# Power_Supplies.net
KiCad netlist of a schematic drawn in Altium Designer
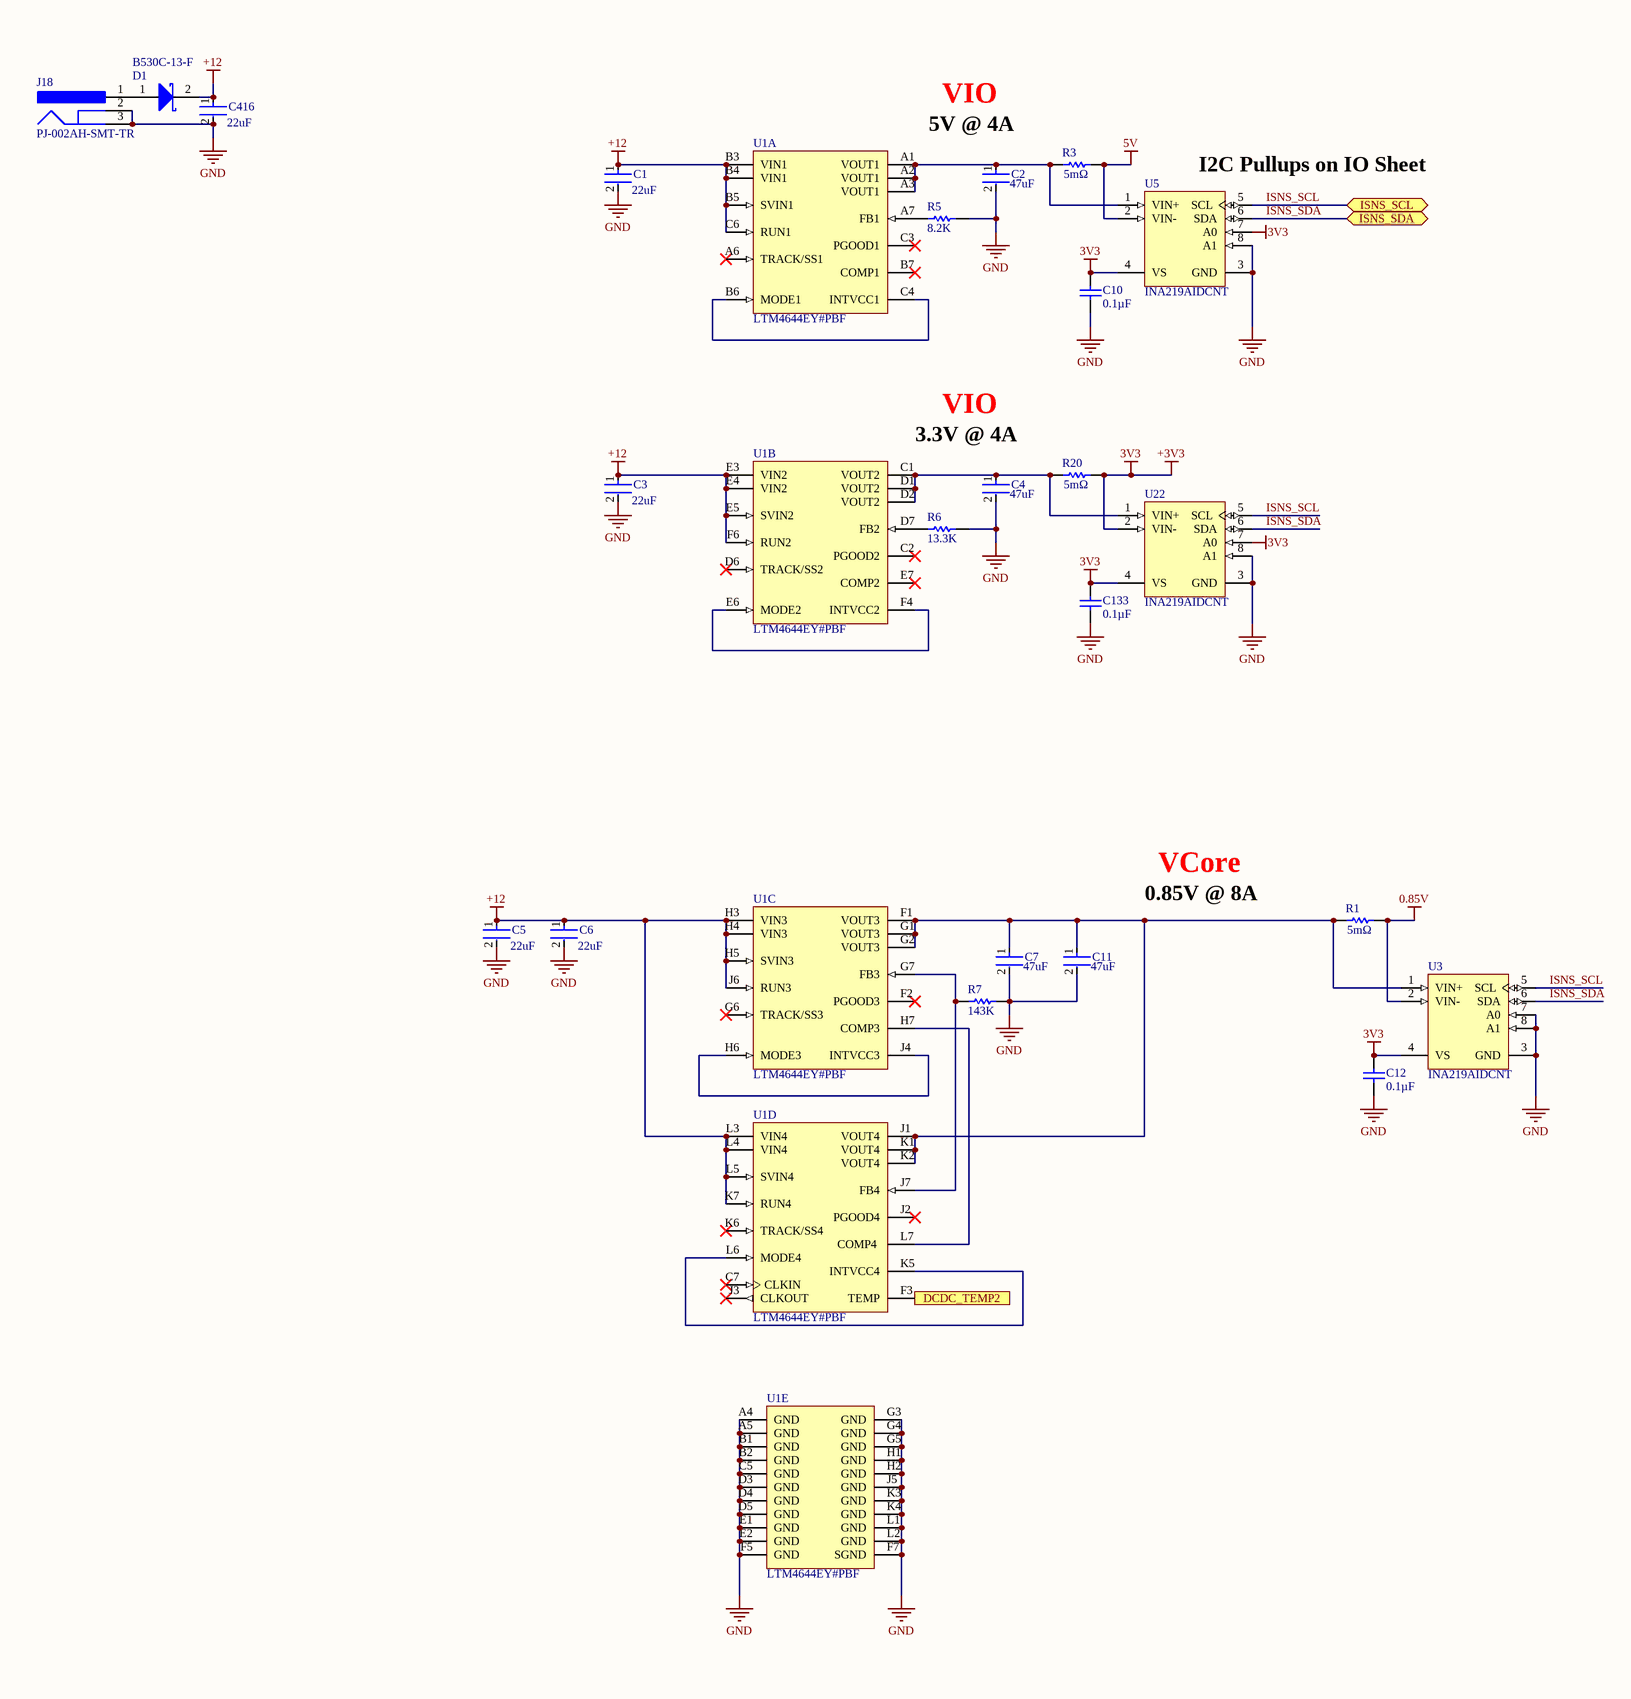
[diagram p0: Power Supplies.SchDoc, left]
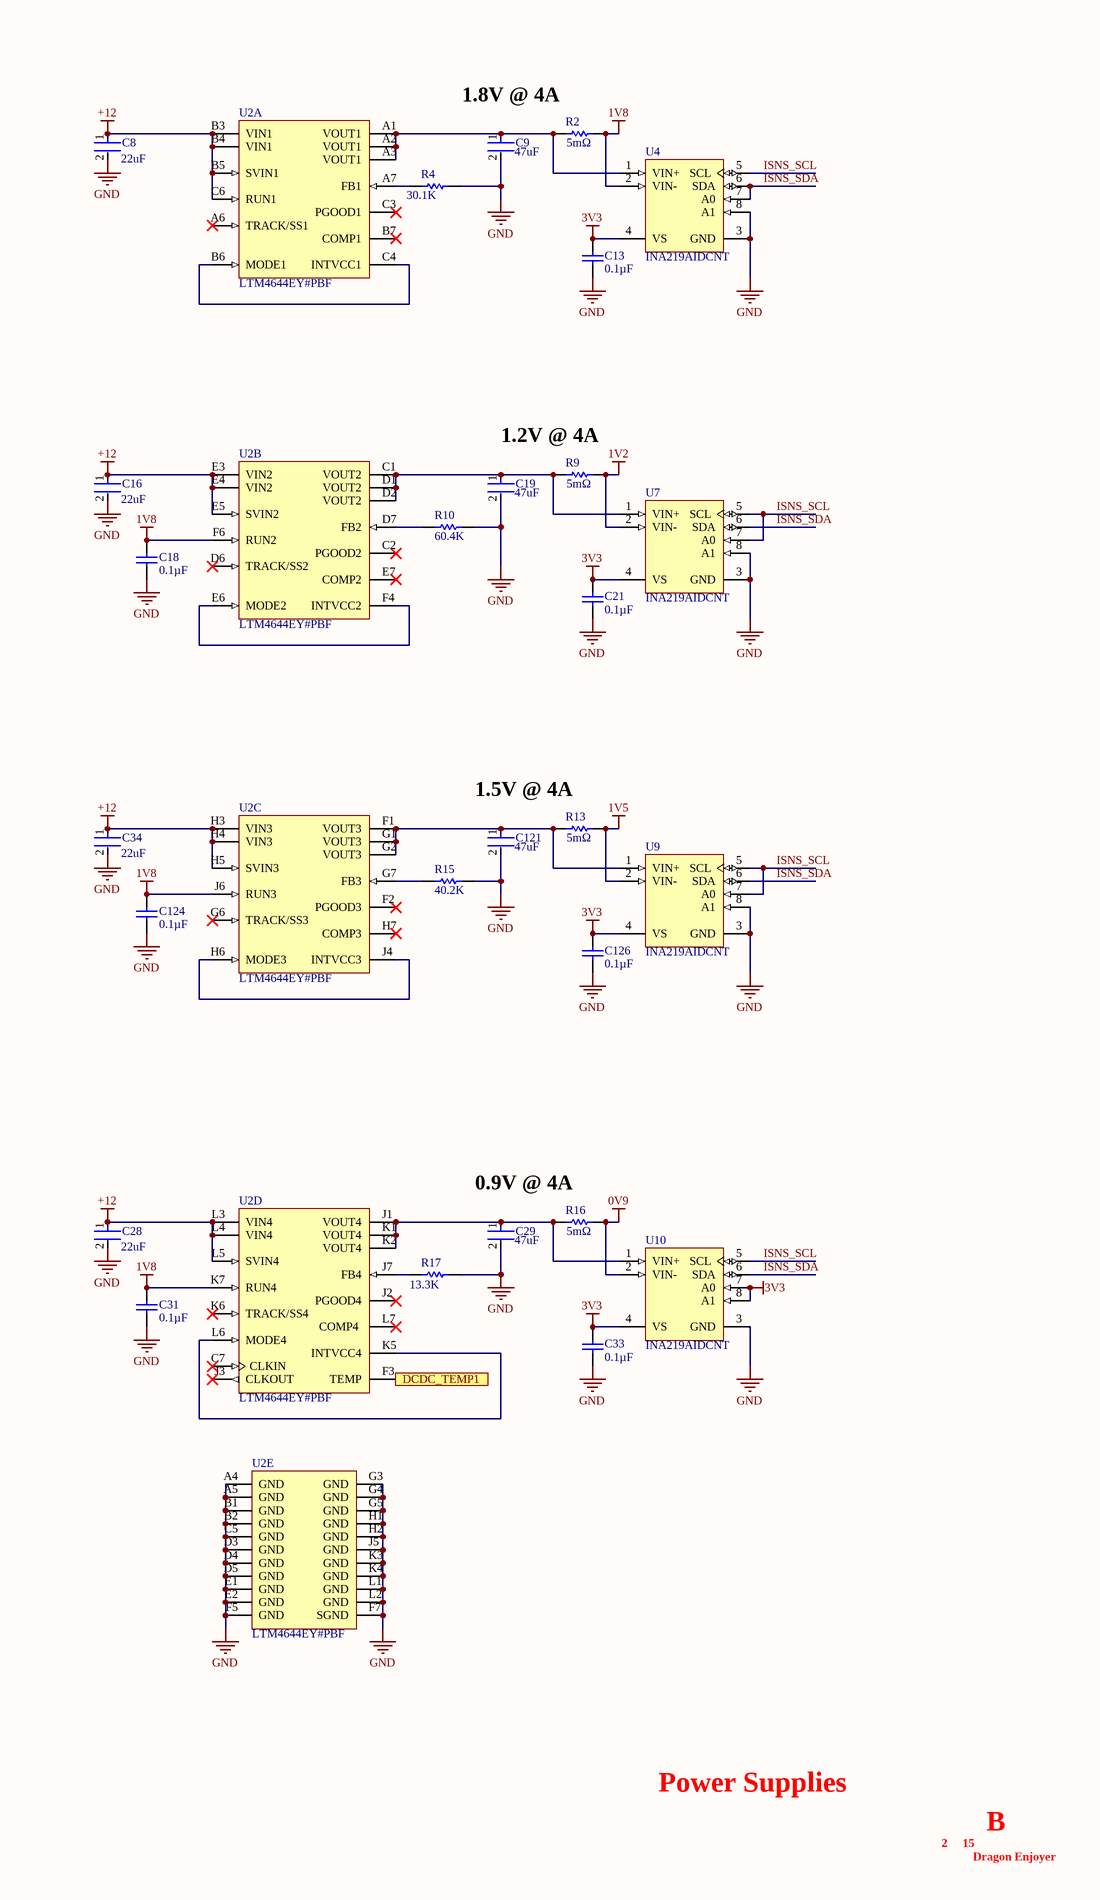
[diagram p1: Power Supplies.SchDoc, right]

(export (version "E")
  (design (tool "Eeschema 10.0.6"))
  (components
    (comp (ref "C1")
      (value "22uF")
      (footprint "FP-CL31H-0_2-MFG")
      (description "CAP CER 22UF 25V X5R 1206")
      (fields
        (field (name "OCTOPART") "https://octopart.com/cl31a226kahnnne-samsung-19832795")
        (field (name "TOLERANCE") "10%")
      )
      (libsource (lib "Altium Content Vault") (part "11868f565c42a9108669ba33697ecf6"))
    )
    (comp (ref "C2")
      (value "GRM31CR60J476ME19L")
      (footprint "FP-GRM31C-0_2-e0_3_0_8-IPC_C")
      (description "Chip Multilayer Ceramic Capacitors for General Purpose, 1206, 47uF, X5R, 15%, 20%, 6.3V")
      (fields
        (field (name "TOLERANCE") "20%")
        (field (name "VOLTAGE") "6.3V")
        (field (name "CAPACITANCE") "47uF")
      )
      (libsource (lib "Altium Content Vault") (part "02cd4be3c70576c341d710602a673aa"))
    )
    (comp (ref "C3")
      (value "22uF")
      (footprint "FP-CL31H-0_2-MFG")
      (description "CAP CER 22UF 25V X5R 1206")
      (fields
        (field (name "OCTOPART") "https://octopart.com/cl31a226kahnnne-samsung-19832795")
        (field (name "TOLERANCE") "10%")
      )
      (libsource (lib "Altium Content Vault") (part "11868f565c42a9108669ba33697ecf6"))
    )
    (comp (ref "C4")
      (value "GRM31CR60J476ME19L")
      (footprint "FP-GRM31C-0_2-e0_3_0_8-IPC_C")
      (description "Chip Multilayer Ceramic Capacitors for General Purpose, 1206, 47uF, X5R, 15%, 20%, 6.3V")
      (fields
        (field (name "TOLERANCE") "20%")
        (field (name "VOLTAGE") "6.3V")
        (field (name "CAPACITANCE") "47uF")
      )
      (libsource (lib "Altium Content Vault") (part "02cd4be3c70576c341d710602a673aa"))
    )
    (comp (ref "C5")
      (value "22uF")
      (footprint "FP-CL31H-0_2-MFG")
      (description "CAP CER 22UF 25V X5R 1206")
      (fields
        (field (name "OCTOPART") "https://octopart.com/cl31a226kahnnne-samsung-19832795")
        (field (name "TOLERANCE") "10%")
      )
      (libsource (lib "Altium Content Vault") (part "11868f565c42a9108669ba33697ecf6"))
    )
    (comp (ref "C6")
      (value "22uF")
      (footprint "FP-CL31H-0_2-MFG")
      (description "CAP CER 22UF 25V X5R 1206")
      (fields
        (field (name "OCTOPART") "https://octopart.com/cl31a226kahnnne-samsung-19832795")
        (field (name "TOLERANCE") "10%")
      )
      (libsource (lib "Altium Content Vault") (part "11868f565c42a9108669ba33697ecf6"))
    )
    (comp (ref "C7")
      (value "GRM31CR60J476ME19L")
      (footprint "FP-GRM31C-0_2-e0_3_0_8-IPC_C")
      (description "Chip Multilayer Ceramic Capacitors for General Purpose, 1206, 47uF, X5R, 15%, 20%, 6.3V")
      (fields
        (field (name "TOLERANCE") "20%")
        (field (name "VOLTAGE") "6.3V")
        (field (name "CAPACITANCE") "47uF")
      )
      (libsource (lib "Altium Content Vault") (part "02cd4be3c70576c341d710602a673aa"))
    )
    (comp (ref "C8")
      (value "22uF")
      (footprint "FP-CL31H-0_2-MFG")
      (description "CAP CER 22UF 25V X5R 1206")
      (fields
        (field (name "OCTOPART") "https://octopart.com/cl31a226kahnnne-samsung-19832795")
        (field (name "TOLERANCE") "10%")
      )
      (libsource (lib "Altium Content Vault") (part "11868f565c42a9108669ba33697ecf6"))
    )
    (comp (ref "C9")
      (value "GRM31CR60J476ME19L")
      (footprint "FP-GRM31C-0_2-e0_3_0_8-IPC_C")
      (description "Chip Multilayer Ceramic Capacitors for General Purpose, 1206, 47uF, X5R, 15%, 20%, 6.3V")
      (fields
        (field (name "TOLERANCE") "20%")
        (field (name "VOLTAGE") "6.3V")
        (field (name "CAPACITANCE") "47uF")
      )
      (libsource (lib "Altium Content Vault") (part "02cd4be3c70576c341d710602a673aa"))
    )
    (comp (ref "C10")
      (value "CC0402ZRY5V8BB104")
      (footprint "CAPC1005X55X25LL05T05")
      (description "Chip Capacitor, 100 nF, -20% to 80%, 25 V, -30 to 85 degC, 0402 (1005 Metric), RoHS, Tape and Reel")
      (fields
        (field (name "TOLERANCE") "-20%,+80%")
        (field (name "CAPACITANCE") "0.1µF")
        (field (name "MANUFACTURER") "Yageo")
      )
      (libsource (lib "Altium Content Vault") (part "CAP-NP-2"))
    )
    (comp (ref "C11")
      (value "GRM31CR60J476ME19L")
      (footprint "FP-GRM31C-0_2-e0_3_0_8-IPC_C")
      (description "Chip Multilayer Ceramic Capacitors for General Purpose, 1206, 47uF, X5R, 15%, 20%, 6.3V")
      (fields
        (field (name "TOLERANCE") "20%")
        (field (name "VOLTAGE") "6.3V")
        (field (name "CAPACITANCE") "47uF")
      )
      (libsource (lib "Altium Content Vault") (part "02cd4be3c70576c341d710602a673aa"))
    )
    (comp (ref "C12")
      (value "CC0402ZRY5V8BB104")
      (footprint "CAPC1005X55X25LL05T05")
      (description "Chip Capacitor, 100 nF, -20% to 80%, 25 V, -30 to 85 degC, 0402 (1005 Metric), RoHS, Tape and Reel")
      (fields
        (field (name "TOLERANCE") "-20%,+80%")
        (field (name "CAPACITANCE") "0.1µF")
        (field (name "MANUFACTURER") "Yageo")
      )
      (libsource (lib "Altium Content Vault") (part "CAP-NP-2"))
    )
    (comp (ref "C13")
      (value "CC0402ZRY5V8BB104")
      (footprint "CAPC1005X55X25LL05T05")
      (description "Chip Capacitor, 100 nF, -20% to 80%, 25 V, -30 to 85 degC, 0402 (1005 Metric), RoHS, Tape and Reel")
      (fields
        (field (name "TOLERANCE") "-20%,+80%")
        (field (name "CAPACITANCE") "0.1µF")
        (field (name "MANUFACTURER") "Yageo")
      )
      (libsource (lib "Altium Content Vault") (part "CAP-NP-2"))
    )
    (comp (ref "C16")
      (value "22uF")
      (footprint "FP-CL31H-0_2-MFG")
      (description "CAP CER 22UF 25V X5R 1206")
      (fields
        (field (name "OCTOPART") "https://octopart.com/cl31a226kahnnne-samsung-19832795")
        (field (name "TOLERANCE") "10%")
      )
      (libsource (lib "Altium Content Vault") (part "11868f565c42a9108669ba33697ecf6"))
    )
    (comp (ref "C18")
      (value "CC0402ZRY5V8BB104")
      (footprint "CAPC1005X55X25LL05T05")
      (description "Chip Capacitor, 100 nF, -20% to 80%, 25 V, -30 to 85 degC, 0402 (1005 Metric), RoHS, Tape and Reel")
      (fields
        (field (name "TOLERANCE") "-20%,+80%")
        (field (name "CAPACITANCE") "0.1µF")
        (field (name "MANUFACTURER") "Yageo")
      )
      (libsource (lib "Altium Content Vault") (part "CAP-NP-2"))
    )
    (comp (ref "C19")
      (value "GRM31CR60J476ME19L")
      (footprint "FP-GRM31C-0_2-e0_3_0_8-IPC_C")
      (description "Chip Multilayer Ceramic Capacitors for General Purpose, 1206, 47uF, X5R, 15%, 20%, 6.3V")
      (fields
        (field (name "TOLERANCE") "20%")
        (field (name "VOLTAGE") "6.3V")
        (field (name "CAPACITANCE") "47uF")
      )
      (libsource (lib "Altium Content Vault") (part "02cd4be3c70576c341d710602a673aa"))
    )
    (comp (ref "C21")
      (value "CC0402ZRY5V8BB104")
      (footprint "CAPC1005X55X25LL05T05")
      (description "Chip Capacitor, 100 nF, -20% to 80%, 25 V, -30 to 85 degC, 0402 (1005 Metric), RoHS, Tape and Reel")
      (fields
        (field (name "TOLERANCE") "-20%,+80%")
        (field (name "CAPACITANCE") "0.1µF")
        (field (name "MANUFACTURER") "Yageo")
      )
      (libsource (lib "Altium Content Vault") (part "CAP-NP-2"))
    )
    (comp (ref "C28")
      (value "22uF")
      (footprint "FP-CL31H-0_2-MFG")
      (description "CAP CER 22UF 25V X5R 1206")
      (fields
        (field (name "OCTOPART") "https://octopart.com/cl31a226kahnnne-samsung-19832795")
        (field (name "TOLERANCE") "10%")
      )
      (libsource (lib "Altium Content Vault") (part "11868f565c42a9108669ba33697ecf6"))
    )
    (comp (ref "C29")
      (value "GRM31CR60J476ME19L")
      (footprint "FP-GRM31C-0_2-e0_3_0_8-IPC_C")
      (description "Chip Multilayer Ceramic Capacitors for General Purpose, 1206, 47uF, X5R, 15%, 20%, 6.3V")
      (fields
        (field (name "TOLERANCE") "20%")
        (field (name "VOLTAGE") "6.3V")
        (field (name "CAPACITANCE") "47uF")
      )
      (libsource (lib "Altium Content Vault") (part "02cd4be3c70576c341d710602a673aa"))
    )
    (comp (ref "C31")
      (value "CC0402ZRY5V8BB104")
      (footprint "CAPC1005X55X25LL05T05")
      (description "Chip Capacitor, 100 nF, -20% to 80%, 25 V, -30 to 85 degC, 0402 (1005 Metric), RoHS, Tape and Reel")
      (fields
        (field (name "TOLERANCE") "-20%,+80%")
        (field (name "CAPACITANCE") "0.1µF")
        (field (name "MANUFACTURER") "Yageo")
      )
      (libsource (lib "Altium Content Vault") (part "CAP-NP-2"))
    )
    (comp (ref "C33")
      (value "CC0402ZRY5V8BB104")
      (footprint "CAPC1005X55X25LL05T05")
      (description "Chip Capacitor, 100 nF, -20% to 80%, 25 V, -30 to 85 degC, 0402 (1005 Metric), RoHS, Tape and Reel")
      (fields
        (field (name "TOLERANCE") "-20%,+80%")
        (field (name "CAPACITANCE") "0.1µF")
        (field (name "MANUFACTURER") "Yageo")
      )
      (libsource (lib "Altium Content Vault") (part "CAP-NP-2"))
    )
    (comp (ref "C34")
      (value "22uF")
      (footprint "FP-CL31H-0_2-MFG")
      (description "CAP CER 22UF 25V X5R 1206")
      (fields
        (field (name "OCTOPART") "https://octopart.com/cl31a226kahnnne-samsung-19832795")
        (field (name "TOLERANCE") "10%")
      )
      (libsource (lib "Altium Content Vault") (part "11868f565c42a9108669ba33697ecf6"))
    )
    (comp (ref "C121")
      (value "GRM31CR60J476ME19L")
      (footprint "FP-GRM31C-0_2-e0_3_0_8-IPC_C")
      (description "Chip Multilayer Ceramic Capacitors for General Purpose, 1206, 47uF, X5R, 15%, 20%, 6.3V")
      (fields
        (field (name "TOLERANCE") "20%")
        (field (name "VOLTAGE") "6.3V")
        (field (name "CAPACITANCE") "47uF")
      )
      (libsource (lib "Altium Content Vault") (part "02cd4be3c70576c341d710602a673aa"))
    )
    (comp (ref "C124")
      (value "CC0402ZRY5V8BB104")
      (footprint "CAPC1005X55X25LL05T05")
      (description "Chip Capacitor, 100 nF, -20% to 80%, 25 V, -30 to 85 degC, 0402 (1005 Metric), RoHS, Tape and Reel")
      (fields
        (field (name "TOLERANCE") "-20%,+80%")
        (field (name "CAPACITANCE") "0.1µF")
        (field (name "MANUFACTURER") "Yageo")
      )
      (libsource (lib "Altium Content Vault") (part "CAP-NP-2"))
    )
    (comp (ref "C126")
      (value "CC0402ZRY5V8BB104")
      (footprint "CAPC1005X55X25LL05T05")
      (description "Chip Capacitor, 100 nF, -20% to 80%, 25 V, -30 to 85 degC, 0402 (1005 Metric), RoHS, Tape and Reel")
      (fields
        (field (name "TOLERANCE") "-20%,+80%")
        (field (name "CAPACITANCE") "0.1µF")
        (field (name "MANUFACTURER") "Yageo")
      )
      (libsource (lib "Altium Content Vault") (part "CAP-NP-2"))
    )
    (comp (ref "C133")
      (value "CC0402ZRY5V8BB104")
      (footprint "CAPC1005X55X25LL05T05")
      (description "Chip Capacitor, 100 nF, -20% to 80%, 25 V, -30 to 85 degC, 0402 (1005 Metric), RoHS, Tape and Reel")
      (fields
        (field (name "TOLERANCE") "-20%,+80%")
        (field (name "CAPACITANCE") "0.1µF")
        (field (name "MANUFACTURER") "Yageo")
      )
      (libsource (lib "Altium Content Vault") (part "CAP-NP-2"))
    )
    (comp (ref "C416")
      (value "22uF")
      (footprint "FP-CL31H-0_2-MFG")
      (description "CAP CER 22UF 25V X5R 1206")
      (fields
        (field (name "OCTOPART") "https://octopart.com/cl31a226kahnnne-samsung-19832795")
        (field (name "TOLERANCE") "10%")
      )
      (libsource (lib "Altium Content Vault") (part "11868f565c42a9108669ba33697ecf6"))
    )
    (comp (ref "D1")
      (value "B530C-13-F")
      (footprint "DIOD-SMC-2_V")
      (libsource (lib "Altium Content Vault") (part "DSKY-AK-2"))
    )
    (comp (ref "J18")
      (value "PJ-002AH-SMT-TR")
      (footprint "CUI-PJ-002AH-4_V")
      (description "DC Power Jack, Right Angle, -25 to 85 degC, 4-Pin 14.8 x 9 x 11 mm SMD, RoHS, Tape and Reel")
      (fields (field (name "MANUFACTURER") "CUIInc.") (field (name "PARTNUMBER") "PJ-002AH"))
      (libsource (lib "Altium Content Vault") (part "JACK-2CD3-RN"))
    )
    (comp (ref "R1")
      (value "5mΩ")
      (footprint "RESC3216X89X64NL25T25")
      (fields (field (name "MANUFACTURER") "Vishay Dale") (field (name "PART NUMBER") "WSL12065L000FEA"))
      (libsource (lib "Altium Content Vault") (part "RES"))
    )
    (comp (ref "R2")
      (value "5mΩ")
      (footprint "RESC3216X89X64NL25T25")
      (fields (field (name "MANUFACTURER") "Vishay Dale") (field (name "PART NUMBER") "WSL12065L000FEA"))
      (libsource (lib "Altium Content Vault") (part "RES"))
    )
    (comp (ref "R3")
      (value "5mΩ")
      (footprint "RESC3216X89X64NL25T25")
      (fields (field (name "MANUFACTURER") "Vishay Dale") (field (name "PART NUMBER") "WSL12065L000FEA"))
      (libsource (lib "Altium Content Vault") (part "RES"))
    )
    (comp (ref "R4")
      (value "30.1K")
      (footprint "RESC1609X55X30ML10T20")
      (fields (field (name "MANUFACTURER") "Vishay Dale") (field (name "PART NUMBER") "TNPW060330K1BEEA"))
      (libsource (lib "Altium Content Vault") (part "RES"))
    )
    (comp (ref "R5")
      (value "8.2K")
      (footprint "RESC1005X40X25ML05T05")
      (fields (field (name "PART NUMBER") "CRCW04028K20FKED") (field (name "MANUFACTURER") "Vishay Dale"))
      (libsource (lib "Altium Content Vault") (part "RES"))
    )
    (comp (ref "R6")
      (value "13.3K")
      (footprint "RESC1005X40X25NL10T10")
      (fields (field (name "MANUFACTURER") "Multicomp") (field (name "PART NUMBER") "MC00625W0402113K3"))
      (libsource (lib "Altium Content Vault") (part "RES"))
    )
    (comp (ref "R7")
      (value "143K")
      (footprint "RESC1005X40X25LL05T05")
      (fields (field (name "PART NUMBER") "ERJ-2RKF1433X") (field (name "MANUFACTURER") "Panasonic"))
      (libsource (lib "Altium Content Vault") (part "RES"))
    )
    (comp (ref "R9")
      (value "5mΩ")
      (footprint "RESC3216X89X64NL25T25")
      (fields (field (name "MANUFACTURER") "Vishay Dale") (field (name "PART NUMBER") "WSL12065L000FEA"))
      (libsource (lib "Altium Content Vault") (part "RES"))
    )
    (comp (ref "R10")
      (value "60.4K")
      (footprint "RESC1608X50X30ML20T20")
      (fields (field (name "PART NUMBER") "RG1608P-6042-B-T1") (field (name "MANUFACTURER") "Susumu"))
      (libsource (lib "Altium Content Vault") (part "RES"))
    )
    (comp (ref "R13")
      (value "5mΩ")
      (footprint "RESC3216X89X64NL25T25")
      (fields (field (name "MANUFACTURER") "Vishay Dale") (field (name "PART NUMBER") "WSL12065L000FEA"))
      (libsource (lib "Altium Content Vault") (part "RES"))
    )
    (comp (ref "R15")
      (value "40.2K")
      (footprint "RESC0603(1608)_M")
      (description "40K2 0.1W 1% 0603 (1608 Metric)  SMD")
      (fields (field (name "TOLERANCE") "1 %") (field (name "POWER") "0.1 W"))
      (libsource (lib "Altium Content Vault") (part "RES"))
    )
    (comp (ref "R16")
      (value "5mΩ")
      (footprint "RESC3216X89X64NL25T25")
      (fields (field (name "MANUFACTURER") "Vishay Dale") (field (name "PART NUMBER") "WSL12065L000FEA"))
      (libsource (lib "Altium Content Vault") (part "RES"))
    )
    (comp (ref "R17")
      (value "13.3K")
      (footprint "RESC1609X55X30ML10T20")
      (fields (field (name "MANUFACTURER") "Vishay Dale") (field (name "PART NUMBER") "TNPW060313K3BEEA"))
      (libsource (lib "Altium Content Vault") (part "RES"))
    )
    (comp (ref "R20")
      (value "5mΩ")
      (footprint "RESC3216X89X64NL25T25")
      (fields (field (name "MANUFACTURER") "Vishay Dale") (field (name "PART NUMBER") "WSL12065L000FEA"))
      (libsource (lib "Altium Content Vault") (part "RES"))
    )
    (comp (ref "U1")
      (value "LTM4644EY#PBF")
      (footprint "LT-BGA-77-05-08-1900_V")
      (description "Quad DC/DC uModule Regulator, 4 A, 4 to 14 V, -40 to 125 degC, 77-Pin BGA, RoHS, Tray")
      (fields (field (name "MANUFACTURER") "Linear Technology"))
      (libsource (lib "Altium Content Vault") (part "LT-LTM4644-77"))
    )
    (comp (ref "U2")
      (value "LTM4644EY#PBF")
      (footprint "LT-BGA-77-05-08-1900_V")
      (description "Quad DC/DC uModule Regulator, 4 A, 4 to 14 V, -40 to 125 degC, 77-Pin BGA, RoHS, Tray")
      (fields (field (name "MANUFACTURER") "Linear Technology"))
      (libsource (lib "Altium Content Vault") (part "LT-LTM4644-77"))
    )
    (comp (ref "U3")
      (value "INA219AIDCNT")
      (footprint "DCN0008A_L")
      (fields (field (name "MANUFACTURER") "Texas Instruments"))
      (libsource (lib "Altium Content Vault") (part "TI-INA219DCN8"))
    )
    (comp (ref "U4")
      (value "INA219AIDCNT")
      (footprint "DCN0008A_L")
      (fields (field (name "MANUFACTURER") "Texas Instruments"))
      (libsource (lib "Altium Content Vault") (part "TI-INA219DCN8"))
    )
    (comp (ref "U5")
      (value "INA219AIDCNT")
      (footprint "DCN0008A_L")
      (fields (field (name "MANUFACTURER") "Texas Instruments"))
      (libsource (lib "Altium Content Vault") (part "TI-INA219DCN8"))
    )
    (comp (ref "U7")
      (value "INA219AIDCNT")
      (footprint "DCN0008A_L")
      (fields (field (name "MANUFACTURER") "Texas Instruments"))
      (libsource (lib "Altium Content Vault") (part "TI-INA219DCN8"))
    )
    (comp (ref "U9")
      (value "INA219AIDCNT")
      (footprint "DCN0008A_L")
      (fields (field (name "MANUFACTURER") "Texas Instruments"))
      (libsource (lib "Altium Content Vault") (part "TI-INA219DCN8"))
    )
    (comp (ref "U10")
      (value "INA219AIDCNT")
      (footprint "DCN0008A_L")
      (fields (field (name "MANUFACTURER") "Texas Instruments"))
      (libsource (lib "Altium Content Vault") (part "TI-INA219DCN8"))
    )
    (comp (ref "U22")
      (value "INA219AIDCNT")
      (footprint "DCN0008A_L")
      (fields (field (name "MANUFACTURER") "Texas Instruments"))
      (libsource (lib "Altium Content Vault") (part "TI-INA219DCN8"))
    )
  )
  (nets
    (net (code "1") (name "+3V3") (class "Default")
      (node (ref "C10") (pin "2") (pinfunction "2_2") (pintype "passive"))
      (node (ref "C12") (pin "2") (pinfunction "2_2") (pintype "passive"))
      (node (ref "C126") (pin "2") (pinfunction "2_2") (pintype "passive"))
      (node (ref "C13") (pin "2") (pinfunction "2_2") (pintype "passive"))
      (node (ref "C133") (pin "2") (pinfunction "2_2") (pintype "passive"))
      (node (ref "C21") (pin "2") (pinfunction "2_2") (pintype "passive"))
      (node (ref "C33") (pin "2") (pinfunction "2_2") (pintype "passive"))
      (node (ref "R20") (pin "2") (pinfunction "2_2") (pintype "passive"))
      (node (ref "U10") (pin "4") (pinfunction "VS_4") (pintype "power_in"))
      (node (ref "U10") (pin "7") (pinfunction "A0_7") (pintype "input"))
      (node (ref "U10") (pin "8") (pinfunction "A1_8") (pintype "input"))
      (node (ref "U22") (pin "2") (pinfunction "VIN-_2") (pintype "input"))
      (node (ref "U22") (pin "4") (pinfunction "VS_4") (pintype "power_in"))
      (node (ref "U22") (pin "7") (pinfunction "A0_7") (pintype "input"))
      (node (ref "U3") (pin "4") (pinfunction "VS_4") (pintype "power_in"))
      (node (ref "U4") (pin "4") (pinfunction "VS_4") (pintype "power_in"))
      (node (ref "U5") (pin "4") (pinfunction "VS_4") (pintype "power_in"))
      (node (ref "U5") (pin "7") (pinfunction "A0_7") (pintype "input"))
      (node (ref "U7") (pin "4") (pinfunction "VS_4") (pintype "power_in"))
      (node (ref "U9") (pin "4") (pinfunction "VS_4") (pintype "power_in"))
    )
    (net (code "2") (name "+12") (class "Default")
      (node (ref "C1") (pin "1") (pinfunction "1_1") (pintype "passive"))
      (node (ref "C16") (pin "1") (pinfunction "1_1") (pintype "passive"))
      (node (ref "C28") (pin "1") (pinfunction "1_1") (pintype "passive"))
      (node (ref "C3") (pin "1") (pinfunction "1_1") (pintype "passive"))
      (node (ref "C34") (pin "1") (pinfunction "1_1") (pintype "passive"))
      (node (ref "C416") (pin "1") (pinfunction "1_1") (pintype "passive"))
      (node (ref "C5") (pin "1") (pinfunction "1_1") (pintype "passive"))
      (node (ref "C6") (pin "1") (pinfunction "1_1") (pintype "passive"))
      (node (ref "C8") (pin "1") (pinfunction "1_1") (pintype "passive"))
      (node (ref "D1") (pin "2") (pinfunction "K_2") (pintype "passive"))
      (node (ref "U1") (pin "B3") (pinfunction "VIN1_B3") (pintype "power_in"))
      (node (ref "U1") (pin "B4") (pinfunction "VIN1_B4") (pintype "power_in"))
      (node (ref "U1") (pin "B5") (pinfunction "SVIN1_B5") (pintype "input"))
      (node (ref "U1") (pin "C6") (pinfunction "RUN1_C6") (pintype "input"))
      (node (ref "U1") (pin "E3") (pinfunction "VIN2_E3") (pintype "power_in"))
      (node (ref "U1") (pin "E4") (pinfunction "VIN2_E4") (pintype "power_in"))
      (node (ref "U1") (pin "E5") (pinfunction "SVIN2_E5") (pintype "input"))
      (node (ref "U1") (pin "F6") (pinfunction "RUN2_F6") (pintype "input"))
      (node (ref "U1") (pin "H3") (pinfunction "VIN3_H3") (pintype "power_in"))
      (node (ref "U1") (pin "H4") (pinfunction "VIN3_H4") (pintype "power_in"))
      (node (ref "U1") (pin "H5") (pinfunction "SVIN3_H5") (pintype "input"))
      (node (ref "U1") (pin "J6") (pinfunction "RUN3_J6") (pintype "input"))
      (node (ref "U1") (pin "K7") (pinfunction "RUN4_K7") (pintype "input"))
      (node (ref "U1") (pin "L3") (pinfunction "VIN4_L3") (pintype "power_in"))
      (node (ref "U1") (pin "L4") (pinfunction "VIN4_L4") (pintype "power_in"))
      (node (ref "U1") (pin "L5") (pinfunction "SVIN4_L5") (pintype "input"))
      (node (ref "U2") (pin "B3") (pinfunction "VIN1_B3") (pintype "power_in"))
      (node (ref "U2") (pin "B4") (pinfunction "VIN1_B4") (pintype "power_in"))
      (node (ref "U2") (pin "B5") (pinfunction "SVIN1_B5") (pintype "input"))
      (node (ref "U2") (pin "C6") (pinfunction "RUN1_C6") (pintype "input"))
      (node (ref "U2") (pin "E3") (pinfunction "VIN2_E3") (pintype "power_in"))
      (node (ref "U2") (pin "E4") (pinfunction "VIN2_E4") (pintype "power_in"))
      (node (ref "U2") (pin "E5") (pinfunction "SVIN2_E5") (pintype "input"))
      (node (ref "U2") (pin "H3") (pinfunction "VIN3_H3") (pintype "power_in"))
      (node (ref "U2") (pin "H4") (pinfunction "VIN3_H4") (pintype "power_in"))
      (node (ref "U2") (pin "H5") (pinfunction "SVIN3_H5") (pintype "input"))
      (node (ref "U2") (pin "L3") (pinfunction "VIN4_L3") (pintype "power_in"))
      (node (ref "U2") (pin "L4") (pinfunction "VIN4_L4") (pintype "power_in"))
      (node (ref "U2") (pin "L5") (pinfunction "SVIN4_L5") (pintype "input"))
    )
    (net (code "3") (name "/DCDC_TEMP1") (class "Default")
      (node (ref "U2") (pin "F3") (pinfunction "TEMP_F3") (pintype "passive"))
    )
    (net (code "4") (name "/DCDC_TEMP2") (class "Default")
      (node (ref "U1") (pin "F3") (pinfunction "TEMP_F3") (pintype "passive"))
    )
    (net (code "5") (name "/ISNS_SCL") (class "Default")
      (node (ref "U10") (pin "5") (pinfunction "SCL_5") (pintype "bidirectional"))
      (node (ref "U22") (pin "5") (pinfunction "SCL_5") (pintype "bidirectional"))
      (node (ref "U3") (pin "5") (pinfunction "SCL_5") (pintype "bidirectional"))
      (node (ref "U4") (pin "5") (pinfunction "SCL_5") (pintype "bidirectional"))
      (node (ref "U5") (pin "5") (pinfunction "SCL_5") (pintype "bidirectional"))
      (node (ref "U7") (pin "5") (pinfunction "SCL_5") (pintype "bidirectional"))
      (node (ref "U7") (pin "7") (pinfunction "A0_7") (pintype "input"))
      (node (ref "U9") (pin "5") (pinfunction "SCL_5") (pintype "bidirectional"))
      (node (ref "U9") (pin "7") (pinfunction "A0_7") (pintype "input"))
    )
    (net (code "6") (name "/ISNS_SDA") (class "Default")
      (node (ref "U10") (pin "6") (pinfunction "SDA_6") (pintype "bidirectional"))
      (node (ref "U22") (pin "6") (pinfunction "SDA_6") (pintype "bidirectional"))
      (node (ref "U3") (pin "6") (pinfunction "SDA_6") (pintype "bidirectional"))
      (node (ref "U4") (pin "6") (pinfunction "SDA_6") (pintype "bidirectional"))
      (node (ref "U4") (pin "7") (pinfunction "A0_7") (pintype "input"))
      (node (ref "U5") (pin "6") (pinfunction "SDA_6") (pintype "bidirectional"))
      (node (ref "U7") (pin "6") (pinfunction "SDA_6") (pintype "bidirectional"))
      (node (ref "U9") (pin "6") (pinfunction "SDA_6") (pintype "bidirectional"))
    )
    (net (code "7") (name "0.85V") (class "Default")
      (node (ref "R1") (pin "2") (pinfunction "2_2") (pintype "passive"))
      (node (ref "U3") (pin "2") (pinfunction "VIN-_2") (pintype "input"))
    )
    (net (code "8") (name "0V9") (class "Default")
      (node (ref "R16") (pin "2") (pinfunction "2_2") (pintype "passive"))
      (node (ref "U10") (pin "2") (pinfunction "VIN-_2") (pintype "input"))
    )
    (net (code "9") (name "1V2") (class "Default")
      (node (ref "R9") (pin "2") (pinfunction "2_2") (pintype "passive"))
      (node (ref "U7") (pin "2") (pinfunction "VIN-_2") (pintype "input"))
    )
    (net (code "10") (name "1V5") (class "Default")
      (node (ref "R13") (pin "2") (pinfunction "2_2") (pintype "passive"))
      (node (ref "U9") (pin "2") (pinfunction "VIN-_2") (pintype "input"))
    )
    (net (code "11") (name "1V8") (class "Default")
      (node (ref "C124") (pin "2") (pinfunction "2_2") (pintype "passive"))
      (node (ref "C18") (pin "2") (pinfunction "2_2") (pintype "passive"))
      (node (ref "C31") (pin "2") (pinfunction "2_2") (pintype "passive"))
      (node (ref "R2") (pin "2") (pinfunction "2_2") (pintype "passive"))
      (node (ref "U2") (pin "F6") (pinfunction "RUN2_F6") (pintype "input"))
      (node (ref "U2") (pin "J6") (pinfunction "RUN3_J6") (pintype "input"))
      (node (ref "U2") (pin "K7") (pinfunction "RUN4_K7") (pintype "input"))
      (node (ref "U4") (pin "2") (pinfunction "VIN-_2") (pintype "input"))
    )
    (net (code "12") (name "5V") (class "Default")
      (node (ref "R3") (pin "2") (pinfunction "2_2") (pintype "passive"))
      (node (ref "U5") (pin "2") (pinfunction "VIN-_2") (pintype "input"))
    )
    (net (code "13") (name "GND") (class "Default")
      (node (ref "C1") (pin "2") (pinfunction "2_2") (pintype "passive"))
      (node (ref "C10") (pin "1") (pinfunction "1_1") (pintype "passive"))
      (node (ref "C11") (pin "2") (pinfunction "2_2") (pintype "passive"))
      (node (ref "C12") (pin "1") (pinfunction "1_1") (pintype "passive"))
      (node (ref "C121") (pin "2") (pinfunction "2_2") (pintype "passive"))
      (node (ref "C124") (pin "1") (pinfunction "1_1") (pintype "passive"))
      (node (ref "C126") (pin "1") (pinfunction "1_1") (pintype "passive"))
      (node (ref "C13") (pin "1") (pinfunction "1_1") (pintype "passive"))
      (node (ref "C133") (pin "1") (pinfunction "1_1") (pintype "passive"))
      (node (ref "C16") (pin "2") (pinfunction "2_2") (pintype "passive"))
      (node (ref "C18") (pin "1") (pinfunction "1_1") (pintype "passive"))
      (node (ref "C19") (pin "2") (pinfunction "2_2") (pintype "passive"))
      (node (ref "C2") (pin "2") (pinfunction "2_2") (pintype "passive"))
      (node (ref "C21") (pin "1") (pinfunction "1_1") (pintype "passive"))
      (node (ref "C28") (pin "2") (pinfunction "2_2") (pintype "passive"))
      (node (ref "C29") (pin "2") (pinfunction "2_2") (pintype "passive"))
      (node (ref "C3") (pin "2") (pinfunction "2_2") (pintype "passive"))
      (node (ref "C31") (pin "1") (pinfunction "1_1") (pintype "passive"))
      (node (ref "C33") (pin "1") (pinfunction "1_1") (pintype "passive"))
      (node (ref "C34") (pin "2") (pinfunction "2_2") (pintype "passive"))
      (node (ref "C4") (pin "2") (pinfunction "2_2") (pintype "passive"))
      (node (ref "C416") (pin "2") (pinfunction "2_2") (pintype "passive"))
      (node (ref "C5") (pin "2") (pinfunction "2_2") (pintype "passive"))
      (node (ref "C6") (pin "2") (pinfunction "2_2") (pintype "passive"))
      (node (ref "C7") (pin "2") (pinfunction "2_2") (pintype "passive"))
      (node (ref "C8") (pin "2") (pinfunction "2_2") (pintype "passive"))
      (node (ref "C9") (pin "2") (pinfunction "2_2") (pintype "passive"))
      (node (ref "J18") (pin "2") (pinfunction "2_2") (pintype "passive"))
      (node (ref "J18") (pin "3") (pinfunction "3_3") (pintype "passive"))
      (node (ref "R10") (pin "1") (pinfunction "1_1") (pintype "passive"))
      (node (ref "R15") (pin "2") (pinfunction "2_2") (pintype "passive"))
      (node (ref "R17") (pin "2") (pinfunction "2_2") (pintype "passive"))
      (node (ref "R4") (pin "2") (pinfunction "2_2") (pintype "passive"))
      (node (ref "R5") (pin "2") (pinfunction "2_2") (pintype "passive"))
      (node (ref "R6") (pin "2") (pinfunction "2_2") (pintype "passive"))
      (node (ref "R7") (pin "2") (pinfunction "2_2") (pintype "passive"))
      (node (ref "U1") (pin "A4") (pinfunction "GND_A4") (pintype "power_in"))
      (node (ref "U1") (pin "A5") (pinfunction "GND_A5") (pintype "power_in"))
      (node (ref "U1") (pin "B1") (pinfunction "GND_B1") (pintype "power_in"))
      (node (ref "U1") (pin "B2") (pinfunction "GND_B2") (pintype "power_in"))
      (node (ref "U1") (pin "C5") (pinfunction "GND_C5") (pintype "power_in"))
      (node (ref "U1") (pin "D3") (pinfunction "GND_D3") (pintype "power_in"))
      (node (ref "U1") (pin "D4") (pinfunction "GND_D4") (pintype "power_in"))
      (node (ref "U1") (pin "D5") (pinfunction "GND_D5") (pintype "power_in"))
      (node (ref "U1") (pin "E1") (pinfunction "GND_E1") (pintype "power_in"))
      (node (ref "U1") (pin "E2") (pinfunction "GND_E2") (pintype "power_in"))
      (node (ref "U1") (pin "F5") (pinfunction "GND_F5") (pintype "power_in"))
      (node (ref "U1") (pin "F7") (pinfunction "SGND_F7") (pintype "power_in"))
      (node (ref "U1") (pin "G3") (pinfunction "GND_G3") (pintype "power_in"))
      (node (ref "U1") (pin "G4") (pinfunction "GND_G4") (pintype "power_in"))
      (node (ref "U1") (pin "G5") (pinfunction "GND_G5") (pintype "power_in"))
      (node (ref "U1") (pin "H1") (pinfunction "GND_H1") (pintype "power_in"))
      (node (ref "U1") (pin "H2") (pinfunction "GND_H2") (pintype "power_in"))
      (node (ref "U1") (pin "J5") (pinfunction "GND_J5") (pintype "power_in"))
      (node (ref "U1") (pin "K3") (pinfunction "GND_K3") (pintype "power_in"))
      (node (ref "U1") (pin "K4") (pinfunction "GND_K4") (pintype "power_in"))
      (node (ref "U1") (pin "L1") (pinfunction "GND_L1") (pintype "power_in"))
      (node (ref "U1") (pin "L2") (pinfunction "GND_L2") (pintype "power_in"))
      (node (ref "U10") (pin "3") (pinfunction "GND_3") (pintype "passive"))
      (node (ref "U2") (pin "A4") (pinfunction "GND_A4") (pintype "power_in"))
      (node (ref "U2") (pin "A5") (pinfunction "GND_A5") (pintype "power_in"))
      (node (ref "U2") (pin "B1") (pinfunction "GND_B1") (pintype "power_in"))
      (node (ref "U2") (pin "B2") (pinfunction "GND_B2") (pintype "power_in"))
      (node (ref "U2") (pin "C5") (pinfunction "GND_C5") (pintype "power_in"))
      (node (ref "U2") (pin "D3") (pinfunction "GND_D3") (pintype "power_in"))
      (node (ref "U2") (pin "D4") (pinfunction "GND_D4") (pintype "power_in"))
      (node (ref "U2") (pin "D5") (pinfunction "GND_D5") (pintype "power_in"))
      (node (ref "U2") (pin "E1") (pinfunction "GND_E1") (pintype "power_in"))
      (node (ref "U2") (pin "E2") (pinfunction "GND_E2") (pintype "power_in"))
      (node (ref "U2") (pin "F5") (pinfunction "GND_F5") (pintype "power_in"))
      (node (ref "U2") (pin "F7") (pinfunction "SGND_F7") (pintype "power_in"))
      (node (ref "U2") (pin "G3") (pinfunction "GND_G3") (pintype "power_in"))
      (node (ref "U2") (pin "G4") (pinfunction "GND_G4") (pintype "power_in"))
      (node (ref "U2") (pin "G5") (pinfunction "GND_G5") (pintype "power_in"))
      (node (ref "U2") (pin "H1") (pinfunction "GND_H1") (pintype "power_in"))
      (node (ref "U2") (pin "H2") (pinfunction "GND_H2") (pintype "power_in"))
      (node (ref "U2") (pin "J5") (pinfunction "GND_J5") (pintype "power_in"))
      (node (ref "U2") (pin "K3") (pinfunction "GND_K3") (pintype "power_in"))
      (node (ref "U2") (pin "K4") (pinfunction "GND_K4") (pintype "power_in"))
      (node (ref "U2") (pin "L1") (pinfunction "GND_L1") (pintype "power_in"))
      (node (ref "U2") (pin "L2") (pinfunction "GND_L2") (pintype "power_in"))
      (node (ref "U22") (pin "3") (pinfunction "GND_3") (pintype "passive"))
      (node (ref "U22") (pin "8") (pinfunction "A1_8") (pintype "input"))
      (node (ref "U3") (pin "3") (pinfunction "GND_3") (pintype "passive"))
      (node (ref "U3") (pin "7") (pinfunction "A0_7") (pintype "input"))
      (node (ref "U3") (pin "8") (pinfunction "A1_8") (pintype "input"))
      (node (ref "U4") (pin "3") (pinfunction "GND_3") (pintype "passive"))
      (node (ref "U4") (pin "8") (pinfunction "A1_8") (pintype "input"))
      (node (ref "U5") (pin "3") (pinfunction "GND_3") (pintype "passive"))
      (node (ref "U5") (pin "8") (pinfunction "A1_8") (pintype "input"))
      (node (ref "U7") (pin "3") (pinfunction "GND_3") (pintype "passive"))
      (node (ref "U7") (pin "8") (pinfunction "A1_8") (pintype "input"))
      (node (ref "U9") (pin "3") (pinfunction "GND_3") (pintype "passive"))
      (node (ref "U9") (pin "8") (pinfunction "A1_8") (pintype "input"))
    )
    (net (code "14") (name "Net-(D1-A)") (class "Default")
      (node (ref "D1") (pin "1") (pinfunction "A_1") (pintype "passive"))
      (node (ref "J18") (pin "1") (pinfunction "1_1") (pintype "passive"))
    )
    (net (code "15") (name "Net-(U1A-FB1)") (class "Default")
      (node (ref "R5") (pin "1") (pinfunction "1_1") (pintype "passive"))
      (node (ref "U1") (pin "A7") (pinfunction "FB1_A7") (pintype "input"))
    )
    (net (code "16") (name "Net-(U1A-INTVCC1)") (class "Default")
      (node (ref "U1") (pin "B6") (pinfunction "MODE1_B6") (pintype "input"))
      (node (ref "U1") (pin "C4") (pinfunction "INTVCC1_C4") (pintype "power_in"))
    )
    (net (code "17") (name "Net-(U1B-FB2)") (class "Default")
      (node (ref "R6") (pin "1") (pinfunction "1_1") (pintype "passive"))
      (node (ref "U1") (pin "D7") (pinfunction "FB2_D7") (pintype "input"))
    )
    (net (code "18") (name "Net-(U1B-INTVCC2)") (class "Default")
      (node (ref "U1") (pin "E6") (pinfunction "MODE2_E6") (pintype "input"))
      (node (ref "U1") (pin "F4") (pinfunction "INTVCC2_F4") (pintype "power_in"))
    )
    (net (code "19") (name "Net-(U1C-COMP3)") (class "Default")
      (node (ref "U1") (pin "H7") (pinfunction "COMP3_H7") (pintype "passive"))
      (node (ref "U1") (pin "L7") (pinfunction "COMP4_L7") (pintype "passive"))
    )
    (net (code "20") (name "Net-(U1C-FB3)") (class "Default")
      (node (ref "R7") (pin "1") (pinfunction "1_1") (pintype "passive"))
      (node (ref "U1") (pin "G7") (pinfunction "FB3_G7") (pintype "input"))
      (node (ref "U1") (pin "J7") (pinfunction "FB4_J7") (pintype "input"))
    )
    (net (code "21") (name "Net-(U1C-INTVCC3)") (class "Default")
      (node (ref "U1") (pin "H6") (pinfunction "MODE3_H6") (pintype "input"))
      (node (ref "U1") (pin "J4") (pinfunction "INTVCC3_J4") (pintype "power_in"))
    )
    (net (code "22") (name "Net-(U1D-INTVCC4)") (class "Default")
      (node (ref "U1") (pin "K5") (pinfunction "INTVCC4_K5") (pintype "power_in"))
      (node (ref "U1") (pin "L6") (pinfunction "MODE4_L6") (pintype "input"))
    )
    (net (code "23") (name "Net-(U2A-FB1)") (class "Default")
      (node (ref "R4") (pin "1") (pinfunction "1_1") (pintype "passive"))
      (node (ref "U2") (pin "A7") (pinfunction "FB1_A7") (pintype "input"))
    )
    (net (code "24") (name "Net-(U2A-INTVCC1)") (class "Default")
      (node (ref "U2") (pin "B6") (pinfunction "MODE1_B6") (pintype "input"))
      (node (ref "U2") (pin "C4") (pinfunction "INTVCC1_C4") (pintype "power_in"))
    )
    (net (code "25") (name "Net-(U2B-FB2)") (class "Default")
      (node (ref "R10") (pin "2") (pinfunction "2_2") (pintype "passive"))
      (node (ref "U2") (pin "D7") (pinfunction "FB2_D7") (pintype "input"))
    )
    (net (code "26") (name "Net-(U2B-INTVCC2)") (class "Default")
      (node (ref "U2") (pin "E6") (pinfunction "MODE2_E6") (pintype "input"))
      (node (ref "U2") (pin "F4") (pinfunction "INTVCC2_F4") (pintype "power_in"))
    )
    (net (code "27") (name "Net-(U2C-FB3)") (class "Default")
      (node (ref "R15") (pin "1") (pinfunction "1_1") (pintype "passive"))
      (node (ref "U2") (pin "G7") (pinfunction "FB3_G7") (pintype "input"))
    )
    (net (code "28") (name "Net-(U2C-INTVCC3)") (class "Default")
      (node (ref "U2") (pin "H6") (pinfunction "MODE3_H6") (pintype "input"))
      (node (ref "U2") (pin "J4") (pinfunction "INTVCC3_J4") (pintype "power_in"))
    )
    (net (code "29") (name "Net-(U2D-FB4)") (class "Default")
      (node (ref "R17") (pin "1") (pinfunction "1_1") (pintype "passive"))
      (node (ref "U2") (pin "J7") (pinfunction "FB4_J7") (pintype "input"))
    )
    (net (code "30") (name "Net-(U2D-INTVCC4)") (class "Default")
      (node (ref "U2") (pin "K5") (pinfunction "INTVCC4_K5") (pintype "power_in"))
      (node (ref "U2") (pin "L6") (pinfunction "MODE4_L6") (pintype "input"))
    )
    (net (code "31") (name "Net-(U3-VIN+)") (class "Default")
      (node (ref "C11") (pin "1") (pinfunction "1_1") (pintype "passive"))
      (node (ref "C7") (pin "1") (pinfunction "1_1") (pintype "passive"))
      (node (ref "R1") (pin "1") (pinfunction "1_1") (pintype "passive"))
      (node (ref "U1") (pin "F1") (pinfunction "VOUT3_F1") (pintype "power_in"))
      (node (ref "U1") (pin "G1") (pinfunction "VOUT3_G1") (pintype "power_in"))
      (node (ref "U1") (pin "G2") (pinfunction "VOUT3_G2") (pintype "power_in"))
      (node (ref "U1") (pin "J1") (pinfunction "VOUT4_J1") (pintype "power_in"))
      (node (ref "U1") (pin "K1") (pinfunction "VOUT4_K1") (pintype "power_in"))
      (node (ref "U1") (pin "K2") (pinfunction "VOUT4_K2") (pintype "power_in"))
      (node (ref "U3") (pin "1") (pinfunction "VIN+_1") (pintype "input"))
    )
    (net (code "32") (name "Net-(U4-VIN+)") (class "Default")
      (node (ref "C9") (pin "1") (pinfunction "1_1") (pintype "passive"))
      (node (ref "R2") (pin "1") (pinfunction "1_1") (pintype "passive"))
      (node (ref "U2") (pin "A1") (pinfunction "VOUT1_A1") (pintype "power_in"))
      (node (ref "U2") (pin "A2") (pinfunction "VOUT1_A2") (pintype "power_in"))
      (node (ref "U2") (pin "A3") (pinfunction "VOUT1_A3") (pintype "power_in"))
      (node (ref "U4") (pin "1") (pinfunction "VIN+_1") (pintype "input"))
    )
    (net (code "33") (name "Net-(U5-VIN+)") (class "Default")
      (node (ref "C2") (pin "1") (pinfunction "1_1") (pintype "passive"))
      (node (ref "R3") (pin "1") (pinfunction "1_1") (pintype "passive"))
      (node (ref "U1") (pin "A1") (pinfunction "VOUT1_A1") (pintype "power_in"))
      (node (ref "U1") (pin "A2") (pinfunction "VOUT1_A2") (pintype "power_in"))
      (node (ref "U1") (pin "A3") (pinfunction "VOUT1_A3") (pintype "power_in"))
      (node (ref "U5") (pin "1") (pinfunction "VIN+_1") (pintype "input"))
    )
    (net (code "34") (name "Net-(U7-VIN+)") (class "Default")
      (node (ref "C19") (pin "1") (pinfunction "1_1") (pintype "passive"))
      (node (ref "R9") (pin "1") (pinfunction "1_1") (pintype "passive"))
      (node (ref "U2") (pin "C1") (pinfunction "VOUT2_C1") (pintype "power_in"))
      (node (ref "U2") (pin "D1") (pinfunction "VOUT2_D1") (pintype "power_in"))
      (node (ref "U2") (pin "D2") (pinfunction "VOUT2_D2") (pintype "power_in"))
      (node (ref "U7") (pin "1") (pinfunction "VIN+_1") (pintype "input"))
    )
    (net (code "35") (name "Net-(U9-VIN+)") (class "Default")
      (node (ref "C121") (pin "1") (pinfunction "1_1") (pintype "passive"))
      (node (ref "R13") (pin "1") (pinfunction "1_1") (pintype "passive"))
      (node (ref "U2") (pin "F1") (pinfunction "VOUT3_F1") (pintype "power_in"))
      (node (ref "U2") (pin "G1") (pinfunction "VOUT3_G1") (pintype "power_in"))
      (node (ref "U2") (pin "G2") (pinfunction "VOUT3_G2") (pintype "power_in"))
      (node (ref "U9") (pin "1") (pinfunction "VIN+_1") (pintype "input"))
    )
    (net (code "36") (name "Net-(U10-VIN+)") (class "Default")
      (node (ref "C29") (pin "1") (pinfunction "1_1") (pintype "passive"))
      (node (ref "R16") (pin "1") (pinfunction "1_1") (pintype "passive"))
      (node (ref "U10") (pin "1") (pinfunction "VIN+_1") (pintype "input"))
      (node (ref "U2") (pin "J1") (pinfunction "VOUT4_J1") (pintype "power_in"))
      (node (ref "U2") (pin "K1") (pinfunction "VOUT4_K1") (pintype "power_in"))
      (node (ref "U2") (pin "K2") (pinfunction "VOUT4_K2") (pintype "power_in"))
    )
    (net (code "37") (name "Net-(U22-VIN+)") (class "Default")
      (node (ref "C4") (pin "1") (pinfunction "1_1") (pintype "passive"))
      (node (ref "R20") (pin "1") (pinfunction "1_1") (pintype "passive"))
      (node (ref "U1") (pin "C1") (pinfunction "VOUT2_C1") (pintype "power_in"))
      (node (ref "U1") (pin "D1") (pinfunction "VOUT2_D1") (pintype "power_in"))
      (node (ref "U1") (pin "D2") (pinfunction "VOUT2_D2") (pintype "power_in"))
      (node (ref "U22") (pin "1") (pinfunction "VIN+_1") (pintype "input"))
    )
    (net (code "38") (name "unconnected-(U1A-COMP1-PadB7)") (class "Default")
      (node (ref "U1") (pin "B7") (pinfunction "COMP1_B7") (pintype "passive+no_connect"))
    )
    (net (code "39") (name "unconnected-(U1A-PGOOD1-PadC3)") (class "Default")
      (node (ref "U1") (pin "C3") (pinfunction "PGOOD1_C3") (pintype "open_collector+no_connect"))
    )
    (net (code "40") (name "unconnected-(U1A-TRACK{slash}SS1-PadA6)") (class "Default")
      (node (ref "U1") (pin "A6") (pinfunction "TRACK/SS1_A6") (pintype "input+no_connect"))
    )
    (net (code "41") (name "unconnected-(U1B-COMP2-PadE7)") (class "Default")
      (node (ref "U1") (pin "E7") (pinfunction "COMP2_E7") (pintype "passive+no_connect"))
    )
    (net (code "42") (name "unconnected-(U1B-PGOOD2-PadC2)") (class "Default")
      (node (ref "U1") (pin "C2") (pinfunction "PGOOD2_C2") (pintype "open_collector+no_connect"))
    )
    (net (code "43") (name "unconnected-(U1B-TRACK{slash}SS2-PadD6)") (class "Default")
      (node (ref "U1") (pin "D6") (pinfunction "TRACK/SS2_D6") (pintype "input+no_connect"))
    )
    (net (code "44") (name "unconnected-(U1C-PGOOD3-PadF2)") (class "Default")
      (node (ref "U1") (pin "F2") (pinfunction "PGOOD3_F2") (pintype "open_collector+no_connect"))
    )
    (net (code "45") (name "unconnected-(U1C-TRACK{slash}SS3-PadG6)") (class "Default")
      (node (ref "U1") (pin "G6") (pinfunction "TRACK/SS3_G6") (pintype "input+no_connect"))
    )
    (net (code "46") (name "unconnected-(U1D-CLKIN-PadC7)") (class "Default")
      (node (ref "U1") (pin "C7") (pinfunction "CLKIN_C7") (pintype "input+no_connect"))
    )
    (net (code "47") (name "unconnected-(U1D-CLKOUT-PadJ3)") (class "Default")
      (node (ref "U1") (pin "J3") (pinfunction "CLKOUT_J3") (pintype "output+no_connect"))
    )
    (net (code "48") (name "unconnected-(U1D-PGOOD4-PadJ2)") (class "Default")
      (node (ref "U1") (pin "J2") (pinfunction "PGOOD4_J2") (pintype "open_collector+no_connect"))
    )
    (net (code "49") (name "unconnected-(U1D-TRACK{slash}SS4-PadK6)") (class "Default")
      (node (ref "U1") (pin "K6") (pinfunction "TRACK/SS4_K6") (pintype "input+no_connect"))
    )
    (net (code "50") (name "unconnected-(U2A-COMP1-PadB7)") (class "Default")
      (node (ref "U2") (pin "B7") (pinfunction "COMP1_B7") (pintype "passive+no_connect"))
    )
    (net (code "51") (name "unconnected-(U2A-PGOOD1-PadC3)") (class "Default")
      (node (ref "U2") (pin "C3") (pinfunction "PGOOD1_C3") (pintype "open_collector+no_connect"))
    )
    (net (code "52") (name "unconnected-(U2A-TRACK{slash}SS1-PadA6)") (class "Default")
      (node (ref "U2") (pin "A6") (pinfunction "TRACK/SS1_A6") (pintype "input+no_connect"))
    )
    (net (code "53") (name "unconnected-(U2B-COMP2-PadE7)") (class "Default")
      (node (ref "U2") (pin "E7") (pinfunction "COMP2_E7") (pintype "passive+no_connect"))
    )
    (net (code "54") (name "unconnected-(U2B-PGOOD2-PadC2)") (class "Default")
      (node (ref "U2") (pin "C2") (pinfunction "PGOOD2_C2") (pintype "open_collector+no_connect"))
    )
    (net (code "55") (name "unconnected-(U2B-TRACK{slash}SS2-PadD6)") (class "Default")
      (node (ref "U2") (pin "D6") (pinfunction "TRACK/SS2_D6") (pintype "input+no_connect"))
    )
    (net (code "56") (name "unconnected-(U2C-COMP3-PadH7)") (class "Default")
      (node (ref "U2") (pin "H7") (pinfunction "COMP3_H7") (pintype "passive+no_connect"))
    )
    (net (code "57") (name "unconnected-(U2C-PGOOD3-PadF2)") (class "Default")
      (node (ref "U2") (pin "F2") (pinfunction "PGOOD3_F2") (pintype "open_collector+no_connect"))
    )
    (net (code "58") (name "unconnected-(U2C-TRACK{slash}SS3-PadG6)") (class "Default")
      (node (ref "U2") (pin "G6") (pinfunction "TRACK/SS3_G6") (pintype "input+no_connect"))
    )
    (net (code "59") (name "unconnected-(U2D-CLKIN-PadC7)") (class "Default")
      (node (ref "U2") (pin "C7") (pinfunction "CLKIN_C7") (pintype "input+no_connect"))
    )
    (net (code "60") (name "unconnected-(U2D-CLKOUT-PadJ3)") (class "Default")
      (node (ref "U2") (pin "J3") (pinfunction "CLKOUT_J3") (pintype "output+no_connect"))
    )
    (net (code "61") (name "unconnected-(U2D-COMP4-PadL7)") (class "Default")
      (node (ref "U2") (pin "L7") (pinfunction "COMP4_L7") (pintype "passive+no_connect"))
    )
    (net (code "62") (name "unconnected-(U2D-PGOOD4-PadJ2)") (class "Default")
      (node (ref "U2") (pin "J2") (pinfunction "PGOOD4_J2") (pintype "open_collector+no_connect"))
    )
    (net (code "63") (name "unconnected-(U2D-TRACK{slash}SS4-PadK6)") (class "Default")
      (node (ref "U2") (pin "K6") (pinfunction "TRACK/SS4_K6") (pintype "input+no_connect"))
    )
  )
)
